# board.net
KiCad netlist of a schematic drawn in EAGLE
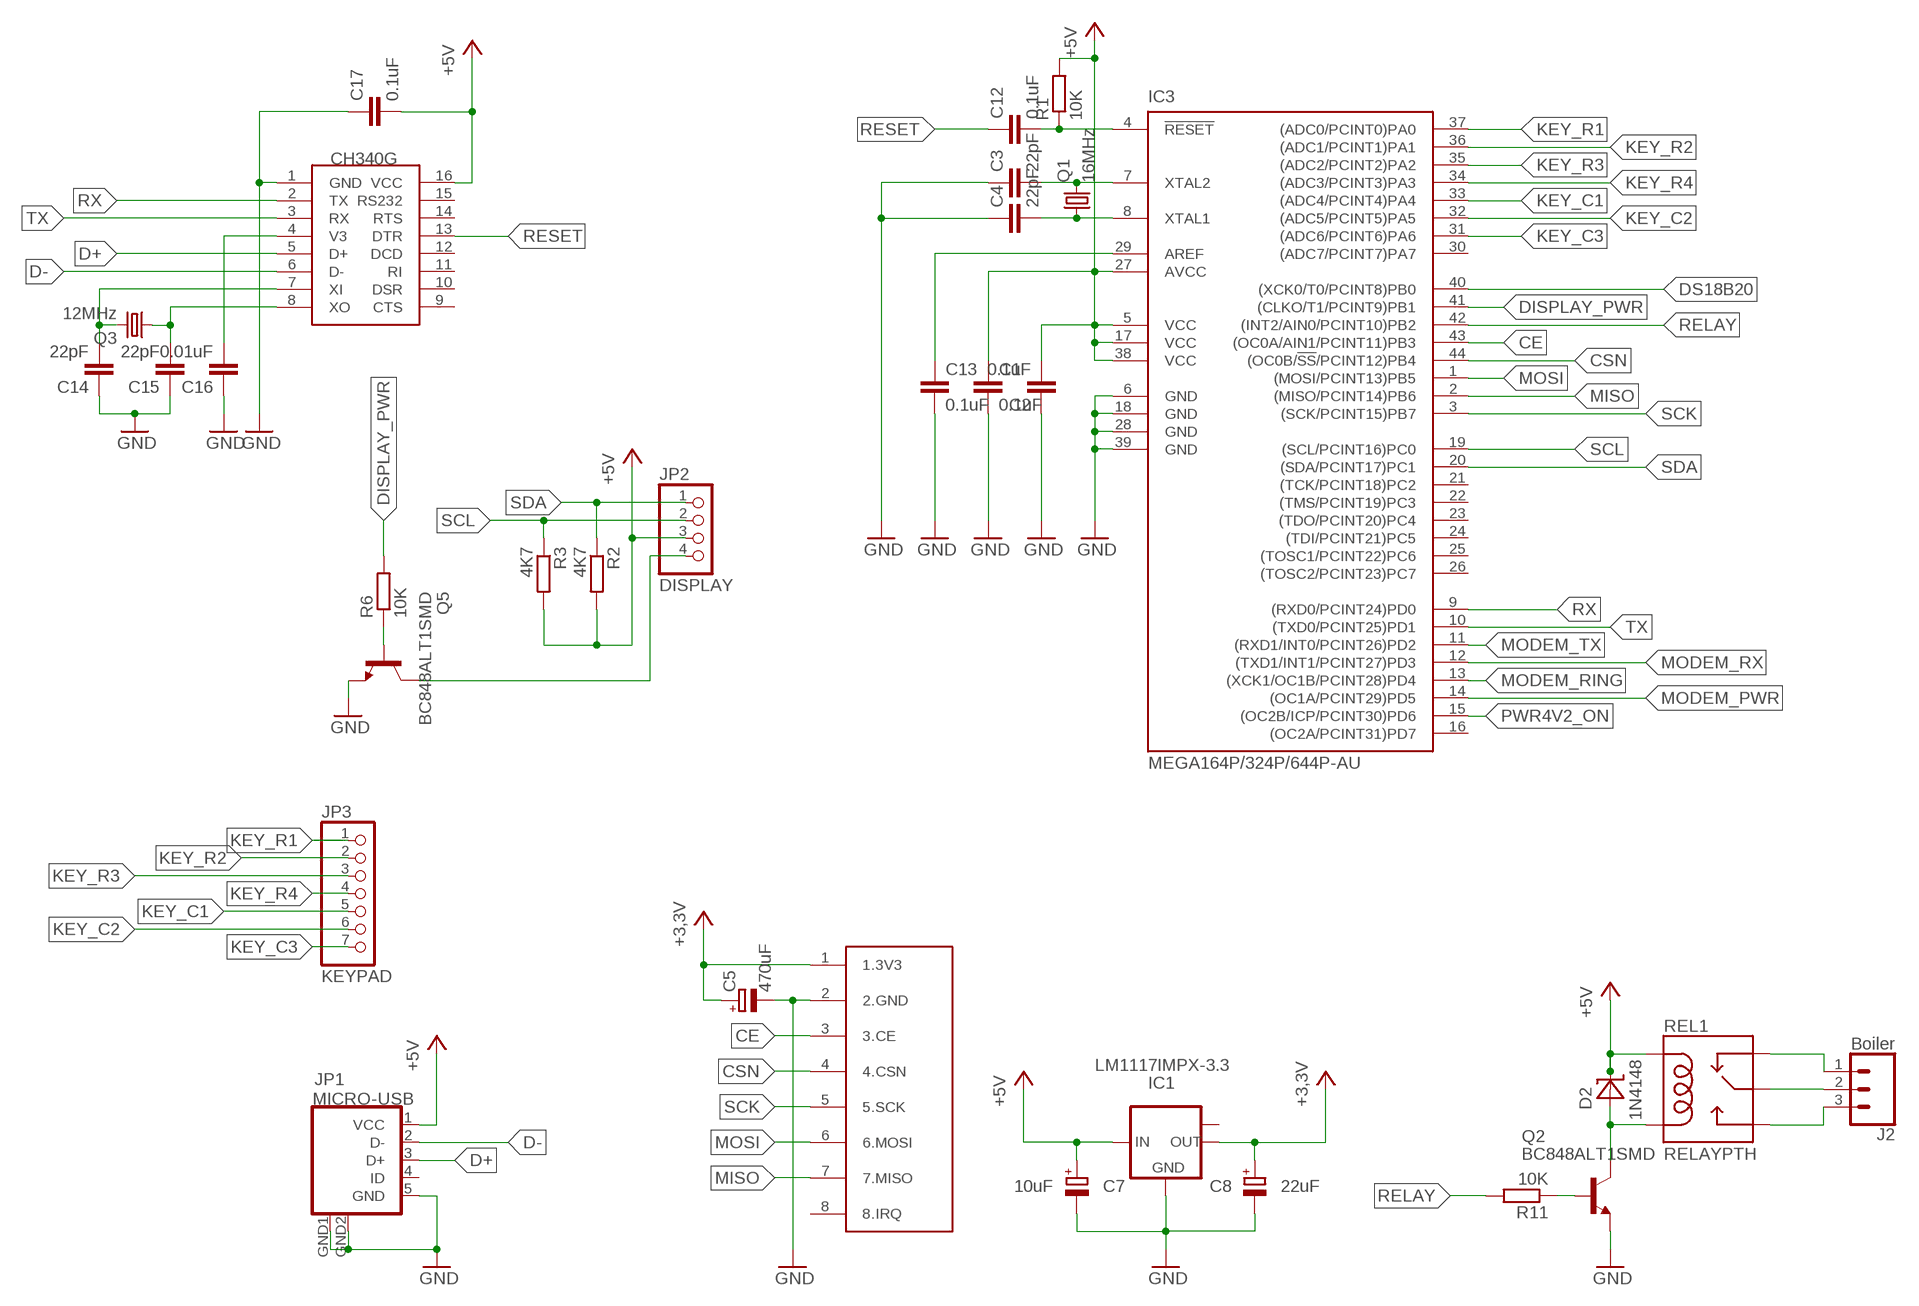
[diagram p0: schematic, sheet 1, part 1 of 2]
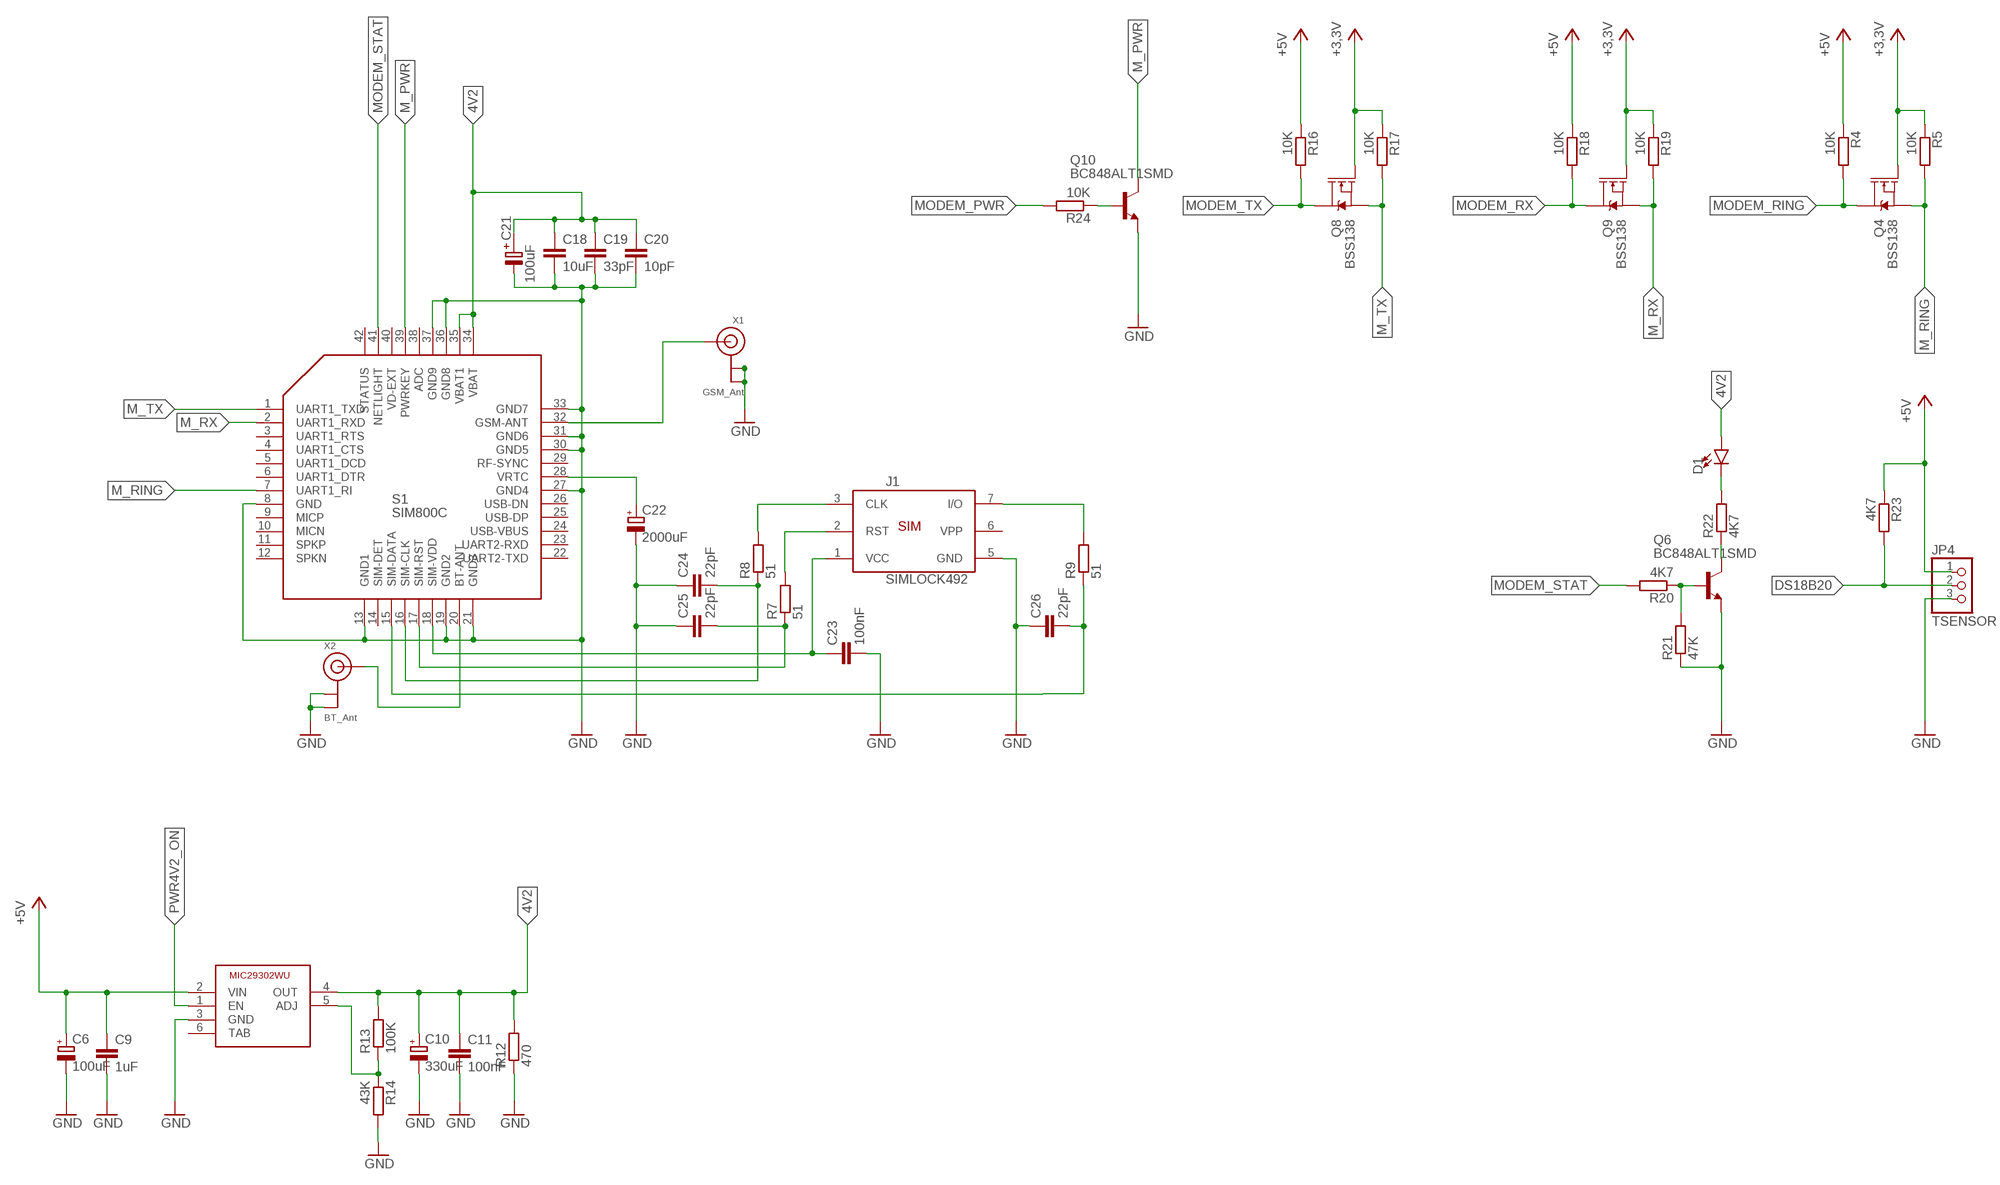
[diagram p1: schematic, sheet 1, part 2 of 2]

(export (version "E")
  (design (tool "Eeschema 10.0.6"))
  (components
    (comp (ref "C1")
      (value "0.1uF")
      (footprint "eagle-import:C1206")
      (libsource (lib "eagle-import") (part "C-EUC1206"))
    )
    (comp (ref "C2")
      (value "0.1uF")
      (footprint "eagle-import:C1206")
      (libsource (lib "eagle-import") (part "C-EUC1206"))
    )
    (comp (ref "C3")
      (value "22pF")
      (footprint "eagle-import:C1206")
      (libsource (lib "eagle-import") (part "C-EUC1206"))
    )
    (comp (ref "C4")
      (value "22pF")
      (footprint "eagle-import:C1206")
      (libsource (lib "eagle-import") (part "C-EUC1206"))
    )
    (comp (ref "C5")
      (value "470uF")
      (footprint "eagle-import:E3,5-8")
      (libsource (lib "eagle-import") (part "CPOL-EUE3.5-8"))
    )
    (comp (ref "C6")
      (value "100uF")
      (footprint "eagle-import:E1,8-4")
      (libsource (lib "eagle-import") (part "CPOL-EUE1.8-4"))
    )
    (comp (ref "C7")
      (value "10uF")
      (footprint "eagle-import:E1,8-4")
      (libsource (lib "eagle-import") (part "CPOL-EUE1.8-4"))
    )
    (comp (ref "C8")
      (value "22uF")
      (footprint "eagle-import:E1,8-4")
      (libsource (lib "eagle-import") (part "CPOL-EUE1.8-4"))
    )
    (comp (ref "C9")
      (value "1uF")
      (footprint "eagle-import:C1206")
      (libsource (lib "eagle-import") (part "C-EUC1206"))
    )
    (comp (ref "C10")
      (value "330uF")
      (footprint "eagle-import:E1,8-4")
      (libsource (lib "eagle-import") (part "CPOL-EUE1.8-4"))
    )
    (comp (ref "C11")
      (value "100nF")
      (footprint "eagle-import:C1206")
      (libsource (lib "eagle-import") (part "C-EUC1206"))
    )
    (comp (ref "C12")
      (value "0.1uF")
      (footprint "eagle-import:C1206")
      (libsource (lib "eagle-import") (part "C-EUC1206"))
    )
    (comp (ref "C13")
      (value "0.1uF")
      (footprint "eagle-import:C1206")
      (libsource (lib "eagle-import") (part "C-EUC1206"))
    )
    (comp (ref "C14")
      (value "22pF")
      (footprint "eagle-import:C1206")
      (libsource (lib "eagle-import") (part "C-EUC1206"))
    )
    (comp (ref "C15")
      (value "22pF")
      (footprint "eagle-import:C1206")
      (libsource (lib "eagle-import") (part "C-EUC1206"))
    )
    (comp (ref "C16")
      (value "0.01uF")
      (footprint "eagle-import:C1206")
      (libsource (lib "eagle-import") (part "C-EUC1206"))
    )
    (comp (ref "C17")
      (value "0.1uF")
      (footprint "eagle-import:C1206")
      (libsource (lib "eagle-import") (part "C-EUC1206"))
    )
    (comp (ref "C18")
      (value "10uF")
      (footprint "eagle-import:C1206")
      (libsource (lib "eagle-import") (part "C-EUC1206"))
    )
    (comp (ref "C19")
      (value "33pF")
      (footprint "eagle-import:C1206")
      (libsource (lib "eagle-import") (part "C-EUC1206"))
    )
    (comp (ref "C20")
      (value "10pF")
      (footprint "eagle-import:C1206")
      (libsource (lib "eagle-import") (part "C-EUC1206"))
    )
    (comp (ref "C21")
      (value "100uF")
      (footprint "eagle-import:TE-D-7343")
      (libsource (lib "eagle-import") (part "C-PR-SMD-TE-D"))
    )
    (comp (ref "C22")
      (value "2000uF")
      (footprint "eagle-import:E3,5-8")
      (libsource (lib "eagle-import") (part "CPOL-EUE3.5-8"))
    )
    (comp (ref "C23")
      (value "100nF")
      (footprint "eagle-import:C1206")
      (libsource (lib "eagle-import") (part "C-EUC1206"))
    )
    (comp (ref "C24")
      (value "22pF")
      (footprint "eagle-import:C1206")
      (libsource (lib "eagle-import") (part "C-EUC1206"))
    )
    (comp (ref "C25")
      (value "22pF")
      (footprint "eagle-import:C1206")
      (libsource (lib "eagle-import") (part "C-EUC1206"))
    )
    (comp (ref "C26")
      (value "22pF")
      (footprint "eagle-import:C1206")
      (libsource (lib "eagle-import") (part "C-EUC1206"))
    )
    (comp (ref "D1")
      (value "LED1206")
      (footprint "eagle-import:LED-1206")
      (libsource (lib "eagle-import") (part "LED1206"))
    )
    (comp (ref "D2")
      (value "1N4148")
      (footprint "eagle-import:SOD323-W")
      (libsource (lib "eagle-import") (part "1206ZENERSOD323"))
    )
    (comp (ref "IC1")
      (value "LM1117IMPX-3.3")
      (footprint "eagle-import:SOT223")
      (libsource (lib "eagle-import") (part "LM1117IMPX-3.3"))
    )
    (comp (ref "IC2")
      (value "MIC29302WU")
      (footprint "eagle-import:TO263-5")
      (fields (field (name "MF") "Microchip"))
      (libsource (lib "eagle-import") (part "MIC29302WU"))
    )
    (comp (ref "IC3")
      (value "MEGA164P/324P/644P-AU")
      (footprint "eagle-import:TQFP44")
      (libsource (lib "eagle-import") (part "MEGA164P/324P/644P-AU"))
    )
    (comp (ref "J1")
      (value "SIMLOCK492")
      (footprint "eagle-import:5002")
      (libsource (lib "eagle-import") (part "SIMLOCK492"))
    )
    (comp (ref "J2")
      (value "Boiler")
      (footprint "eagle-import:SCREWTERMINAL-5MM-3")
      (libsource (lib "eagle-import") (part "CONN_03-SCREW-5MM"))
    )
    (comp (ref "JP1")
      (value "MICRO-USB")
      (footprint "eagle-import:MICRO-USB")
      (libsource (lib "eagle-import") (part "MICRO-USB"))
    )
    (comp (ref "JP2")
      (value "DISPLAY")
      (footprint "eagle-import:1X04")
      (libsource (lib "eagle-import") (part "PINHD-1X4"))
    )
    (comp (ref "JP3")
      (value "KEYPAD")
      (footprint "eagle-import:1X07")
      (libsource (lib "eagle-import") (part "PINHD-1X7"))
    )
    (comp (ref "JP4")
      (value "TSENSOR")
      (footprint "eagle-import:1X03")
      (libsource (lib "eagle-import") (part "PINHD-1X3"))
    )
    (comp (ref "Q1")
      (value "16MHz")
      (footprint "eagle-import:HC49_S")
      (libsource (lib "eagle-import") (part "CRYTALHC49S"))
    )
    (comp (ref "Q2")
      (value "BC848ALT1SMD")
      (footprint "eagle-import:SOT23")
      (libsource (lib "eagle-import") (part "BC848SMDALT1"))
    )
    (comp (ref "Q3")
      (value "12MHz")
      (footprint "eagle-import:HC49_S")
      (libsource (lib "eagle-import") (part "CRYTALHC49S"))
    )
    (comp (ref "Q4")
      (value "BSS138")
      (footprint "eagle-import:SOT23-3")
      (libsource (lib "eagle-import") (part "MOSFET-NCH-BSS138"))
    )
    (comp (ref "Q5")
      (value "BC848ALT1SMD")
      (footprint "eagle-import:SOT23")
      (libsource (lib "eagle-import") (part "BC848SMDALT1"))
    )
    (comp (ref "Q6")
      (value "BC848ALT1SMD")
      (footprint "eagle-import:SOT23")
      (libsource (lib "eagle-import") (part "BC848SMDALT1"))
    )
    (comp (ref "Q8")
      (value "BSS138")
      (footprint "eagle-import:SOT23-3")
      (libsource (lib "eagle-import") (part "MOSFET-NCH-BSS138"))
    )
    (comp (ref "Q9")
      (value "BSS138")
      (footprint "eagle-import:SOT23-3")
      (libsource (lib "eagle-import") (part "MOSFET-NCH-BSS138"))
    )
    (comp (ref "Q10")
      (value "BC848ALT1SMD")
      (footprint "eagle-import:SOT23")
      (libsource (lib "eagle-import") (part "BC848SMDALT1"))
    )
    (comp (ref "R1")
      (value "10K")
      (footprint "eagle-import:R1206")
      (libsource (lib "eagle-import") (part "R-EU_R1206"))
    )
    (comp (ref "R2")
      (value "4K7")
      (footprint "eagle-import:R1206")
      (libsource (lib "eagle-import") (part "R-EU_R1206"))
    )
    (comp (ref "R3")
      (value "4K7")
      (footprint "eagle-import:R1206")
      (libsource (lib "eagle-import") (part "R-EU_R1206"))
    )
    (comp (ref "R4")
      (value "10K")
      (footprint "eagle-import:R1206")
      (libsource (lib "eagle-import") (part "R-EU_R1206"))
    )
    (comp (ref "R5")
      (value "10K")
      (footprint "eagle-import:R1206")
      (libsource (lib "eagle-import") (part "R-EU_R1206"))
    )
    (comp (ref "R6")
      (value "10K")
      (footprint "eagle-import:R1206")
      (libsource (lib "eagle-import") (part "R-EU_R1206"))
    )
    (comp (ref "R7")
      (value "51")
      (footprint "eagle-import:R1206")
      (libsource (lib "eagle-import") (part "R-EU_R1206"))
    )
    (comp (ref "R8")
      (value "51")
      (footprint "eagle-import:R1206")
      (libsource (lib "eagle-import") (part "R-EU_R1206"))
    )
    (comp (ref "R9")
      (value "51")
      (footprint "eagle-import:R1206")
      (libsource (lib "eagle-import") (part "R-EU_R1206"))
    )
    (comp (ref "R11")
      (value "10K")
      (footprint "eagle-import:R1206")
      (libsource (lib "eagle-import") (part "R-EU_R1206"))
    )
    (comp (ref "R12")
      (value "470")
      (footprint "eagle-import:R1206")
      (libsource (lib "eagle-import") (part "R-EU_R1206"))
    )
    (comp (ref "R13")
      (value "100K")
      (footprint "eagle-import:R1206")
      (libsource (lib "eagle-import") (part "R-EU_R1206"))
    )
    (comp (ref "R14")
      (value "43K")
      (footprint "eagle-import:R1206")
      (libsource (lib "eagle-import") (part "R-EU_R1206"))
    )
    (comp (ref "R16")
      (value "10K")
      (footprint "eagle-import:R1206")
      (libsource (lib "eagle-import") (part "R-EU_R1206"))
    )
    (comp (ref "R17")
      (value "10K")
      (footprint "eagle-import:R1206")
      (libsource (lib "eagle-import") (part "R-EU_R1206"))
    )
    (comp (ref "R18")
      (value "10K")
      (footprint "eagle-import:R1206")
      (libsource (lib "eagle-import") (part "R-EU_R1206"))
    )
    (comp (ref "R19")
      (value "10K")
      (footprint "eagle-import:R1206")
      (libsource (lib "eagle-import") (part "R-EU_R1206"))
    )
    (comp (ref "R20")
      (value "4K7")
      (footprint "eagle-import:R1206")
      (libsource (lib "eagle-import") (part "R-EU_R1206"))
    )
    (comp (ref "R21")
      (value "47K")
      (footprint "eagle-import:R1206")
      (libsource (lib "eagle-import") (part "R-EU_R1206"))
    )
    (comp (ref "R22")
      (value "4K7")
      (footprint "eagle-import:R1206")
      (libsource (lib "eagle-import") (part "R-EU_R1206"))
    )
    (comp (ref "R23")
      (value "4K7")
      (footprint "eagle-import:R1206")
      (libsource (lib "eagle-import") (part "R-EU_R1206"))
    )
    (comp (ref "R24")
      (value "10K")
      (footprint "eagle-import:R1206")
      (libsource (lib "eagle-import") (part "R-EU_R1206"))
    )
    (comp (ref "REL1")
      (value "RELAYPTH")
      (footprint "eagle-import:SRD-05VDC-SL-C")
      (libsource (lib "eagle-import") (part "RELAYPTH"))
    )
    (comp (ref "S1")
      (value "SIM800C")
      (footprint "eagle-import:SIM800C")
      (libsource (lib "eagle-import") (part "SIM800C"))
    )
    (comp (ref "U$1")
      (value "CH340G")
      (footprint "eagle-import:SOIC16")
      (libsource (lib "eagle-import") (part "CH340G"))
    )
    (comp (ref "U$3")
      (value "NRF24L01+")
      (footprint "eagle-import:NRF24L01+")
      (libsource (lib "eagle-import") (part "NRF24L01+"))
    )
    (comp (ref "X1")
      (value "GSM_Ant")
      (footprint "eagle-import:U.FL")
      (libsource (lib "eagle-import") (part "ANTENNA_U.FL"))
    )
    (comp (ref "X2")
      (value "BT_Ant")
      (footprint "eagle-import:U.FL")
      (libsource (lib "eagle-import") (part "ANTENNA_U.FL"))
    )
  )
  (nets
    (net (code "1") (name "+3,3V") (class "Default")
      (node (ref "C5") (pin "+") (pinfunction "+_+") (pintype "passive"))
      (node (ref "C8") (pin "+") (pinfunction "+_+") (pintype "passive"))
      (node (ref "IC1") (pin "2") (pinfunction "OUT_2") (pintype "passive"))
      (node (ref "Q4") (pin "1") (pinfunction "G_1") (pintype "bidirectional"))
      (node (ref "Q8") (pin "1") (pinfunction "G_1") (pintype "bidirectional"))
      (node (ref "Q9") (pin "1") (pinfunction "G_1") (pintype "bidirectional"))
      (node (ref "R17") (pin "1") (pinfunction "1_1") (pintype "passive"))
      (node (ref "R19") (pin "1") (pinfunction "1_1") (pintype "passive"))
      (node (ref "R5") (pin "1") (pinfunction "1_1") (pintype "passive"))
      (node (ref "U$3") (pin "1") (pinfunction "1.3V3_1") (pintype "bidirectional"))
    )
    (net (code "2") (name "+5V") (class "Default")
      (node (ref "C1") (pin "1") (pinfunction "1_1") (pintype "passive"))
      (node (ref "C17") (pin "2") (pinfunction "2_2") (pintype "passive"))
      (node (ref "C2") (pin "2") (pinfunction "2_2") (pintype "passive"))
      (node (ref "C6") (pin "+") (pinfunction "+_+") (pintype "passive"))
      (node (ref "C7") (pin "+") (pinfunction "+_+") (pintype "passive"))
      (node (ref "C9") (pin "1") (pinfunction "1_1") (pintype "passive"))
      (node (ref "D2") (pin "C") (pinfunction "C_C") (pintype "passive"))
      (node (ref "IC1") (pin "3") (pinfunction "IN_3") (pintype "input"))
      (node (ref "IC2") (pin "2") (pinfunction "VIN_2") (pintype "bidirectional"))
      (node (ref "IC3") (pin "17") (pinfunction "VCC_17") (pintype "power_in"))
      (node (ref "IC3") (pin "27") (pinfunction "AVCC_27") (pintype "power_in"))
      (node (ref "IC3") (pin "38") (pinfunction "VCC_38") (pintype "power_in"))
      (node (ref "IC3") (pin "5") (pinfunction "VCC_5") (pintype "power_in"))
      (node (ref "JP1") (pin "1") (pinfunction "VCC_1") (pintype "power_in"))
      (node (ref "JP2") (pin "3") (pinfunction "3_3") (pintype "passive"))
      (node (ref "JP4") (pin "1") (pinfunction "1_1") (pintype "passive"))
      (node (ref "R1") (pin "2") (pinfunction "2_2") (pintype "passive"))
      (node (ref "R16") (pin "1") (pinfunction "1_1") (pintype "passive"))
      (node (ref "R18") (pin "1") (pinfunction "1_1") (pintype "passive"))
      (node (ref "R2") (pin "2") (pinfunction "2_2") (pintype "passive"))
      (node (ref "R23") (pin "1") (pinfunction "1_1") (pintype "passive"))
      (node (ref "R3") (pin "2") (pinfunction "2_2") (pintype "passive"))
      (node (ref "R4") (pin "1") (pinfunction "1_1") (pintype "passive"))
      (node (ref "REL1") (pin "COIL1") (pinfunction "COIL1_COIL1") (pintype "bidirectional"))
      (node (ref "U$1") (pin "16") (pinfunction "VCC_16") (pintype "bidirectional"))
    )
    (net (code "3") (name "4V2") (class "Default")
      (node (ref "C10") (pin "+") (pinfunction "+_+") (pintype "passive"))
      (node (ref "C11") (pin "1") (pinfunction "1_1") (pintype "passive"))
      (node (ref "C18") (pin "1") (pinfunction "1_1") (pintype "passive"))
      (node (ref "C19") (pin "1") (pinfunction "1_1") (pintype "passive"))
      (node (ref "C20") (pin "1") (pinfunction "1_1") (pintype "passive"))
      (node (ref "C21") (pin "+") (pinfunction "+_+") (pintype "passive"))
      (node (ref "D1") (pin "A") (pinfunction "A_A") (pintype "passive"))
      (node (ref "IC2") (pin "4") (pinfunction "OUT_4") (pintype "bidirectional"))
      (node (ref "R12") (pin "2") (pinfunction "2_2") (pintype "passive"))
      (node (ref "R13") (pin "2") (pinfunction "2_2") (pintype "passive"))
      (node (ref "S1") (pin "34") (pinfunction "VBAT_34") (pintype "power_in"))
      (node (ref "S1") (pin "35") (pinfunction "VBAT1_35") (pintype "power_in"))
    )
    (net (code "4") (name "CE") (class "Default")
      (node (ref "IC3") (pin "43") (pinfunction "(OC0A/AIN1/PCINT11)PB3_43") (pintype "bidirectional"))
      (node (ref "U$3") (pin "3") (pinfunction "3.CE_3") (pintype "bidirectional"))
    )
    (net (code "5") (name "CSN") (class "Default")
      (node (ref "IC3") (pin "44") (pinfunction "(OC0B/~{SS}/PCINT12)PB4_44") (pintype "bidirectional"))
      (node (ref "U$3") (pin "4") (pinfunction "4.CSN_4") (pintype "bidirectional"))
    )
    (net (code "6") (name "D+") (class "Default")
      (node (ref "JP1") (pin "3") (pinfunction "D+_3") (pintype "bidirectional"))
      (node (ref "U$1") (pin "5") (pinfunction "D+_5") (pintype "bidirectional"))
    )
    (net (code "7") (name "D-") (class "Default")
      (node (ref "JP1") (pin "2") (pinfunction "D-_2") (pintype "bidirectional"))
      (node (ref "U$1") (pin "6") (pinfunction "D-_6") (pintype "bidirectional"))
    )
    (net (code "8") (name "DISPLAY_PWR") (class "Default")
      (node (ref "IC3") (pin "41") (pinfunction "(CLKO/T1/PCINT9)PB1_41") (pintype "bidirectional"))
      (node (ref "R6") (pin "2") (pinfunction "2_2") (pintype "passive"))
    )
    (net (code "9") (name "DS18B20") (class "Default")
      (node (ref "IC3") (pin "40") (pinfunction "(XCK0/T0/PCINT8)PB0_40") (pintype "bidirectional"))
      (node (ref "JP4") (pin "2") (pinfunction "2_2") (pintype "passive"))
      (node (ref "R23") (pin "2") (pinfunction "2_2") (pintype "passive"))
    )
    (net (code "10") (name "GND") (class "Default")
      (node (ref "C1") (pin "2") (pinfunction "2_2") (pintype "passive"))
      (node (ref "C10") (pin "-") (pinfunction "-_-") (pintype "passive"))
      (node (ref "C11") (pin "2") (pinfunction "2_2") (pintype "passive"))
      (node (ref "C13") (pin "2") (pinfunction "2_2") (pintype "passive"))
      (node (ref "C14") (pin "1") (pinfunction "1_1") (pintype "passive"))
      (node (ref "C15") (pin "1") (pinfunction "1_1") (pintype "passive"))
      (node (ref "C16") (pin "1") (pinfunction "1_1") (pintype "passive"))
      (node (ref "C17") (pin "1") (pinfunction "1_1") (pintype "passive"))
      (node (ref "C18") (pin "2") (pinfunction "2_2") (pintype "passive"))
      (node (ref "C19") (pin "2") (pinfunction "2_2") (pintype "passive"))
      (node (ref "C2") (pin "1") (pinfunction "1_1") (pintype "passive"))
      (node (ref "C20") (pin "2") (pinfunction "2_2") (pintype "passive"))
      (node (ref "C21") (pin "-") (pinfunction "-_-") (pintype "passive"))
      (node (ref "C22") (pin "-") (pinfunction "-_-") (pintype "passive"))
      (node (ref "C23") (pin "2") (pinfunction "2_2") (pintype "passive"))
      (node (ref "C24") (pin "1") (pinfunction "1_1") (pintype "passive"))
      (node (ref "C25") (pin "1") (pinfunction "1_1") (pintype "passive"))
      (node (ref "C26") (pin "1") (pinfunction "1_1") (pintype "passive"))
      (node (ref "C3") (pin "1") (pinfunction "1_1") (pintype "passive"))
      (node (ref "C4") (pin "1") (pinfunction "1_1") (pintype "passive"))
      (node (ref "C5") (pin "-") (pinfunction "-_-") (pintype "passive"))
      (node (ref "C6") (pin "-") (pinfunction "-_-") (pintype "passive"))
      (node (ref "C7") (pin "-") (pinfunction "-_-") (pintype "passive"))
      (node (ref "C8") (pin "-") (pinfunction "-_-") (pintype "passive"))
      (node (ref "C9") (pin "2") (pinfunction "2_2") (pintype "passive"))
      (node (ref "IC1") (pin "1") (pinfunction "GND_1") (pintype "input"))
      (node (ref "IC2") (pin "3") (pinfunction "GND_3") (pintype "bidirectional"))
      (node (ref "IC3") (pin "18") (pinfunction "GND_18") (pintype "power_in"))
      (node (ref "IC3") (pin "28") (pinfunction "GND_28") (pintype "power_in"))
      (node (ref "IC3") (pin "39") (pinfunction "GND_39") (pintype "power_in"))
      (node (ref "IC3") (pin "6") (pinfunction "GND_6") (pintype "power_in"))
      (node (ref "J1") (pin "5") (pinfunction "GND_5") (pintype "bidirectional"))
      (node (ref "JP1") (pin "5") (pinfunction "GND_5") (pintype "power_in"))
      (node (ref "JP1") (pin "GND1") (pinfunction "GND_GND1") (pintype "power_in"))
      (node (ref "JP1") (pin "GND2") (pinfunction "GND_GND2") (pintype "power_in"))
      (node (ref "JP4") (pin "3") (pinfunction "3_3") (pintype "passive"))
      (node (ref "Q10") (pin "2") (pinfunction "E_2") (pintype "passive"))
      (node (ref "Q2") (pin "2") (pinfunction "E_2") (pintype "passive"))
      (node (ref "Q5") (pin "2") (pinfunction "E_2") (pintype "passive"))
      (node (ref "Q6") (pin "2") (pinfunction "E_2") (pintype "passive"))
      (node (ref "R12") (pin "1") (pinfunction "1_1") (pintype "passive"))
      (node (ref "R14") (pin "2") (pinfunction "2_2") (pintype "passive"))
      (node (ref "R21") (pin "1") (pinfunction "1_1") (pintype "passive"))
      (node (ref "S1") (pin "13") (pinfunction "GND1_13") (pintype "power_in"))
      (node (ref "S1") (pin "19") (pinfunction "GND2_19") (pintype "power_in"))
      (node (ref "S1") (pin "21") (pinfunction "GND3_21") (pintype "power_in"))
      (node (ref "S1") (pin "27") (pinfunction "GND4_27") (pintype "power_in"))
      (node (ref "S1") (pin "30") (pinfunction "GND5_30") (pintype "power_in"))
      (node (ref "S1") (pin "31") (pinfunction "GND6_31") (pintype "power_in"))
      (node (ref "S1") (pin "33") (pinfunction "GND7_33") (pintype "power_in"))
      (node (ref "S1") (pin "36") (pinfunction "GND8_36") (pintype "power_in"))
      (node (ref "S1") (pin "37") (pinfunction "GND9_37") (pintype "power_in"))
      (node (ref "S1") (pin "8") (pinfunction "GND_8") (pintype "power_in"))
      (node (ref "U$1") (pin "1") (pinfunction "GND_1") (pintype "bidirectional"))
      (node (ref "U$3") (pin "2") (pinfunction "2.GND_2") (pintype "bidirectional"))
      (node (ref "X1") (pin "1") (pinfunction "GND_1") (pintype "passive"))
      (node (ref "X1") (pin "2") (pinfunction "GND_2") (pintype "passive"))
      (node (ref "X2") (pin "1") (pinfunction "GND_1") (pintype "passive"))
      (node (ref "X2") (pin "2") (pinfunction "GND_2") (pintype "passive"))
    )
    (net (code "11") (name "KEY_C1") (class "Default")
      (node (ref "IC3") (pin "33") (pinfunction "(ADC4/PCINT4)PA4_33") (pintype "bidirectional"))
      (node (ref "JP3") (pin "5") (pinfunction "5_5") (pintype "passive"))
    )
    (net (code "12") (name "KEY_C2") (class "Default")
      (node (ref "IC3") (pin "32") (pinfunction "(ADC5/PCINT5)PA5_32") (pintype "bidirectional"))
      (node (ref "JP3") (pin "6") (pinfunction "6_6") (pintype "passive"))
    )
    (net (code "13") (name "KEY_C3") (class "Default")
      (node (ref "IC3") (pin "31") (pinfunction "(ADC6/PCINT6)PA6_31") (pintype "bidirectional"))
      (node (ref "JP3") (pin "7") (pinfunction "7_7") (pintype "passive"))
    )
    (net (code "14") (name "KEY_R1") (class "Default")
      (node (ref "IC3") (pin "37") (pinfunction "(ADC0/PCINT0)PA0_37") (pintype "bidirectional"))
      (node (ref "JP3") (pin "1") (pinfunction "1_1") (pintype "passive"))
    )
    (net (code "15") (name "KEY_R2") (class "Default")
      (node (ref "IC3") (pin "36") (pinfunction "(ADC1/PCINT1)PA1_36") (pintype "bidirectional"))
      (node (ref "JP3") (pin "2") (pinfunction "2_2") (pintype "passive"))
    )
    (net (code "16") (name "KEY_R3") (class "Default")
      (node (ref "IC3") (pin "35") (pinfunction "(ADC2/PCINT2)PA2_35") (pintype "bidirectional"))
      (node (ref "JP3") (pin "3") (pinfunction "3_3") (pintype "passive"))
    )
    (net (code "17") (name "KEY_R4") (class "Default")
      (node (ref "IC3") (pin "34") (pinfunction "(ADC3/PCINT3)PA3_34") (pintype "bidirectional"))
      (node (ref "JP3") (pin "4") (pinfunction "4_4") (pintype "passive"))
    )
    (net (code "18") (name "MISO") (class "Default")
      (node (ref "IC3") (pin "2") (pinfunction "(MISO/PCINT14)PB6_2") (pintype "bidirectional"))
      (node (ref "U$3") (pin "7") (pinfunction "7.MISO_7") (pintype "bidirectional"))
    )
    (net (code "19") (name "MODEM_PWR") (class "Default")
      (node (ref "IC3") (pin "14") (pinfunction "(OC1A/PCINT29)PD5_14") (pintype "bidirectional"))
      (node (ref "R24") (pin "2") (pinfunction "2_2") (pintype "passive"))
    )
    (net (code "20") (name "MODEM_RING") (class "Default")
      (node (ref "IC3") (pin "13") (pinfunction "(XCK1/OC1B/PCINT28)PD4_13") (pintype "bidirectional"))
      (node (ref "Q4") (pin "3") (pinfunction "D_3") (pintype "bidirectional"))
      (node (ref "R4") (pin "2") (pinfunction "2_2") (pintype "passive"))
    )
    (net (code "21") (name "MODEM_RX") (class "Default")
      (node (ref "IC3") (pin "12") (pinfunction "(TXD1/INT1/PCINT27)PD3_12") (pintype "bidirectional"))
      (node (ref "Q9") (pin "3") (pinfunction "D_3") (pintype "bidirectional"))
      (node (ref "R18") (pin "2") (pinfunction "2_2") (pintype "passive"))
    )
    (net (code "22") (name "MODEM_STAT") (class "Default")
      (node (ref "R20") (pin "2") (pinfunction "2_2") (pintype "passive"))
      (node (ref "S1") (pin "41") (pinfunction "NETLIGHT_41") (pintype "bidirectional"))
    )
    (net (code "23") (name "MODEM_TX") (class "Default")
      (node (ref "IC3") (pin "11") (pinfunction "(RXD1/INT0/PCINT26)PD2_11") (pintype "bidirectional"))
      (node (ref "Q8") (pin "3") (pinfunction "D_3") (pintype "bidirectional"))
      (node (ref "R16") (pin "2") (pinfunction "2_2") (pintype "passive"))
    )
    (net (code "24") (name "MOSI") (class "Default")
      (node (ref "IC3") (pin "1") (pinfunction "(MOSI/PCINT13)PB5_1") (pintype "bidirectional"))
      (node (ref "U$3") (pin "6") (pinfunction "6.MOSI_6") (pintype "bidirectional"))
    )
    (net (code "25") (name "M_PWR") (class "Default")
      (node (ref "Q10") (pin "3") (pinfunction "C_3") (pintype "passive"))
      (node (ref "S1") (pin "39") (pinfunction "PWRKEY_39") (pintype "bidirectional"))
    )
    (net (code "26") (name "M_RING") (class "Default")
      (node (ref "Q4") (pin "2") (pinfunction "S_2") (pintype "bidirectional"))
      (node (ref "R5") (pin "2") (pinfunction "2_2") (pintype "passive"))
      (node (ref "S1") (pin "7") (pinfunction "UART1_RI_7") (pintype "bidirectional"))
    )
    (net (code "27") (name "M_RX") (class "Default")
      (node (ref "Q9") (pin "2") (pinfunction "S_2") (pintype "bidirectional"))
      (node (ref "R19") (pin "2") (pinfunction "2_2") (pintype "passive"))
      (node (ref "S1") (pin "2") (pinfunction "UART1_RXD_2") (pintype "bidirectional"))
    )
    (net (code "28") (name "M_TX") (class "Default")
      (node (ref "Q8") (pin "2") (pinfunction "S_2") (pintype "bidirectional"))
      (node (ref "R17") (pin "2") (pinfunction "2_2") (pintype "passive"))
      (node (ref "S1") (pin "1") (pinfunction "UART1_TXD_1") (pintype "bidirectional"))
    )
    (net (code "29") (name "Net-(D1-PadC)") (class "Default")
      (node (ref "D1") (pin "C") (pinfunction "C_C") (pintype "passive"))
      (node (ref "R22") (pin "2") (pinfunction "2_2") (pintype "passive"))
    )
    (net (code "30") (name "Net-(IC2-ADJ)") (class "Default")
      (node (ref "IC2") (pin "5") (pinfunction "ADJ_5") (pintype "bidirectional"))
      (node (ref "R13") (pin "1") (pinfunction "1_1") (pintype "passive"))
      (node (ref "R14") (pin "1") (pinfunction "1_1") (pintype "passive"))
    )
    (net (code "31") (name "Net-(IC3-AREF)") (class "Default")
      (node (ref "C13") (pin "1") (pinfunction "1_1") (pintype "passive"))
      (node (ref "IC3") (pin "29") (pinfunction "AREF_29") (pintype "power_in"))
    )
    (net (code "32") (name "Net-(IC3-XTAL1)") (class "Default")
      (node (ref "C4") (pin "2") (pinfunction "2_2") (pintype "passive"))
      (node (ref "IC3") (pin "8") (pinfunction "XTAL1_8") (pintype "input"))
      (node (ref "Q1") (pin "1") (pinfunction "1_1") (pintype "passive"))
    )
    (net (code "33") (name "Net-(IC3-XTAL2)") (class "Default")
      (node (ref "C3") (pin "2") (pinfunction "2_2") (pintype "passive"))
      (node (ref "IC3") (pin "7") (pinfunction "XTAL2_7") (pintype "output"))
      (node (ref "Q1") (pin "2") (pinfunction "2_2") (pintype "passive"))
    )
    (net (code "34") (name "Net-(IC3-~{RESET})") (class "Default")
      (node (ref "C12") (pin "2") (pinfunction "2_2") (pintype "passive"))
      (node (ref "IC3") (pin "4") (pinfunction "~{RESET}_4") (pintype "input"))
      (node (ref "R1") (pin "1") (pinfunction "1_1") (pintype "passive"))
    )
    (net (code "35") (name "Net-(J1-CLK)") (class "Default")
      (node (ref "J1") (pin "3") (pinfunction "CLK_3") (pintype "bidirectional"))
      (node (ref "R8") (pin "2") (pinfunction "2_2") (pintype "passive"))
    )
    (net (code "36") (name "Net-(J1-I{slash}O)") (class "Default")
      (node (ref "J1") (pin "7") (pinfunction "I/O_7") (pintype "bidirectional"))
      (node (ref "R9") (pin "2") (pinfunction "2_2") (pintype "passive"))
    )
    (net (code "37") (name "Net-(J1-RST)") (class "Default")
      (node (ref "J1") (pin "2") (pinfunction "RST_2") (pintype "bidirectional"))
      (node (ref "R7") (pin "2") (pinfunction "2_2") (pintype "passive"))
    )
    (net (code "38") (name "Net-(J1-VCC)") (class "Default")
      (node (ref "C23") (pin "1") (pinfunction "1_1") (pintype "passive"))
      (node (ref "J1") (pin "1") (pinfunction "VCC_1") (pintype "bidirectional"))
      (node (ref "S1") (pin "18") (pinfunction "SIM-VDD_18") (pintype "bidirectional"))
    )
    (net (code "39") (name "Net-(J2-Pad2)") (class "Default")
      (node (ref "J2") (pin "2") (pinfunction "2_2") (pintype "passive"))
      (node (ref "REL1") (pin "SWCOMMON") (pinfunction "SWCOMMON_SWCOMMON") (pintype "bidirectional"))
    )
    (net (code "40") (name "Net-(J2-Pad3)") (class "Default")
      (node (ref "J2") (pin "3") (pinfunction "3_3") (pintype "passive"))
      (node (ref "REL1") (pin "SWOPEN") (pinfunction "SWOPEN_SWOPEN") (pintype "bidirectional"))
    )
    (net (code "41") (name "Net-(Q2-B)") (class "Default")
      (node (ref "Q2") (pin "1") (pinfunction "B_1") (pintype "passive"))
      (node (ref "R11") (pin "1") (pinfunction "1_1") (pintype "passive"))
    )
    (net (code "42") (name "Net-(Q2-C)") (class "Default")
      (node (ref "D2") (pin "A") (pinfunction "A_A") (pintype "passive"))
      (node (ref "Q2") (pin "3") (pinfunction "C_3") (pintype "passive"))
      (node (ref "REL1") (pin "COIL0") (pinfunction "COIL0_COIL0") (pintype "bidirectional"))
    )
    (net (code "43") (name "Net-(Q5-B)") (class "Default")
      (node (ref "Q5") (pin "1") (pinfunction "B_1") (pintype "passive"))
      (node (ref "R6") (pin "1") (pinfunction "1_1") (pintype "passive"))
    )
    (net (code "44") (name "Net-(Q5-C)") (class "Default")
      (node (ref "JP2") (pin "4") (pinfunction "4_4") (pintype "passive"))
      (node (ref "Q5") (pin "3") (pinfunction "C_3") (pintype "passive"))
    )
    (net (code "45") (name "Net-(Q6-B)") (class "Default")
      (node (ref "Q6") (pin "1") (pinfunction "B_1") (pintype "passive"))
      (node (ref "R20") (pin "1") (pinfunction "1_1") (pintype "passive"))
      (node (ref "R21") (pin "2") (pinfunction "2_2") (pintype "passive"))
    )
    (net (code "46") (name "Net-(Q6-C)") (class "Default")
      (node (ref "Q6") (pin "3") (pinfunction "C_3") (pintype "passive"))
      (node (ref "R22") (pin "1") (pinfunction "1_1") (pintype "passive"))
    )
    (net (code "47") (name "Net-(Q10-B)") (class "Default")
      (node (ref "Q10") (pin "1") (pinfunction "B_1") (pintype "passive"))
      (node (ref "R24") (pin "1") (pinfunction "1_1") (pintype "passive"))
    )
    (net (code "48") (name "Net-(REL1-SWCLOSE)") (class "Default")
      (node (ref "J2") (pin "1") (pinfunction "1_1") (pintype "passive"))
      (node (ref "REL1") (pin "SWCLOSED") (pinfunction "SWCLOSE_SWCLOSED") (pintype "bidirectional"))
    )
    (net (code "49") (name "Net-(S1-BT-ANT)") (class "Default")
      (node (ref "S1") (pin "20") (pinfunction "BT-ANT_20") (pintype "bidirectional"))
      (node (ref "X2") (pin "3") (pinfunction "SIGNAL_3") (pintype "passive"))
    )
    (net (code "50") (name "Net-(S1-GSM-ANT)") (class "Default")
      (node (ref "S1") (pin "32") (pinfunction "GSM-ANT_32") (pintype "bidirectional"))
      (node (ref "X1") (pin "3") (pinfunction "SIGNAL_3") (pintype "passive"))
    )
    (net (code "51") (name "Net-(S1-SIM-CLK)") (class "Default")
      (node (ref "C24") (pin "2") (pinfunction "2_2") (pintype "passive"))
      (node (ref "R8") (pin "1") (pinfunction "1_1") (pintype "passive"))
      (node (ref "S1") (pin "16") (pinfunction "SIM-CLK_16") (pintype "bidirectional"))
    )
    (net (code "52") (name "Net-(S1-SIM-DATA)") (class "Default")
      (node (ref "C26") (pin "2") (pinfunction "2_2") (pintype "passive"))
      (node (ref "R9") (pin "1") (pinfunction "1_1") (pintype "passive"))
      (node (ref "S1") (pin "15") (pinfunction "SIM-DATA_15") (pintype "bidirectional"))
    )
    (net (code "53") (name "Net-(S1-SIM-RST)") (class "Default")
      (node (ref "C25") (pin "2") (pinfunction "2_2") (pintype "passive"))
      (node (ref "R7") (pin "1") (pinfunction "1_1") (pintype "passive"))
      (node (ref "S1") (pin "17") (pinfunction "SIM-RST_17") (pintype "bidirectional"))
    )
    (net (code "54") (name "Net-(S1-VRTC)") (class "Default")
      (node (ref "C22") (pin "+") (pinfunction "+_+") (pintype "passive"))
      (node (ref "S1") (pin "28") (pinfunction "VRTC_28") (pintype "bidirectional"))
    )
    (net (code "55") (name "Net-(U$1-V3)") (class "Default")
      (node (ref "C16") (pin "2") (pinfunction "2_2") (pintype "passive"))
      (node (ref "U$1") (pin "4") (pinfunction "V3_4") (pintype "bidirectional"))
    )
    (net (code "56") (name "Net-(U$1-XI)") (class "Default")
      (node (ref "C14") (pin "2") (pinfunction "2_2") (pintype "passive"))
      (node (ref "Q3") (pin "2") (pinfunction "2_2") (pintype "passive"))
      (node (ref "U$1") (pin "7") (pinfunction "XI_7") (pintype "bidirectional"))
    )
    (net (code "57") (name "Net-(U$1-XO)") (class "Default")
      (node (ref "C15") (pin "2") (pinfunction "2_2") (pintype "passive"))
      (node (ref "Q3") (pin "1") (pinfunction "1_1") (pintype "passive"))
      (node (ref "U$1") (pin "8") (pinfunction "XO_8") (pintype "bidirectional"))
    )
    (net (code "58") (name "PWR4V2_ON") (class "Default")
      (node (ref "IC2") (pin "1") (pinfunction "EN_1") (pintype "bidirectional"))
      (node (ref "IC3") (pin "15") (pinfunction "(OC2B/ICP/PCINT30)PD6_15") (pintype "bidirectional"))
    )
    (net (code "59") (name "RELAY") (class "Default")
      (node (ref "IC3") (pin "42") (pinfunction "(INT2/AIN0/PCINT10)PB2_42") (pintype "bidirectional"))
      (node (ref "R11") (pin "2") (pinfunction "2_2") (pintype "passive"))
    )
    (net (code "60") (name "RESET") (class "Default")
      (node (ref "C12") (pin "1") (pinfunction "1_1") (pintype "passive"))
      (node (ref "U$1") (pin "13") (pinfunction "DTR_13") (pintype "bidirectional"))
    )
    (net (code "61") (name "RX") (class "Default")
      (node (ref "IC3") (pin "9") (pinfunction "(RXD0/PCINT24)PD0_9") (pintype "bidirectional"))
      (node (ref "U$1") (pin "2") (pinfunction "TX_2") (pintype "bidirectional"))
    )
    (net (code "62") (name "SCK") (class "Default")
      (node (ref "IC3") (pin "3") (pinfunction "(SCK/PCINT15)PB7_3") (pintype "bidirectional"))
      (node (ref "U$3") (pin "5") (pinfunction "5.SCK_5") (pintype "bidirectional"))
    )
    (net (code "63") (name "SCL") (class "Default")
      (node (ref "IC3") (pin "19") (pinfunction "(SCL/PCINT16)PC0_19") (pintype "bidirectional"))
      (node (ref "JP2") (pin "2") (pinfunction "2_2") (pintype "passive"))
      (node (ref "R3") (pin "1") (pinfunction "1_1") (pintype "passive"))
    )
    (net (code "64") (name "SDA") (class "Default")
      (node (ref "IC3") (pin "20") (pinfunction "(SDA/PCINT17)PC1_20") (pintype "bidirectional"))
      (node (ref "JP2") (pin "1") (pinfunction "1_1") (pintype "passive"))
      (node (ref "R2") (pin "1") (pinfunction "1_1") (pintype "passive"))
    )
    (net (code "65") (name "TX") (class "Default")
      (node (ref "IC3") (pin "10") (pinfunction "(TXD0/PCINT25)PD1_10") (pintype "bidirectional"))
      (node (ref "U$1") (pin "3") (pinfunction "RX_3") (pintype "bidirectional"))
    )
    (net (code "66") (name "unconnected-(IC1-OUT1-PadTAB)") (class "Default")
      (node (ref "IC1") (pin "TAB") (pinfunction "OUT1_TAB") (pintype "passive"))
    )
    (net (code "67") (name "unconnected-(IC2-TAB-Pad6)") (class "Default")
      (node (ref "IC2") (pin "6") (pinfunction "TAB_6") (pintype "bidirectional"))
    )
    (net (code "68") (name "unconnected-(IC3-(ADC7{slash}PCINT7)PA7-Pad30)") (class "Default")
      (node (ref "IC3") (pin "30") (pinfunction "(ADC7/PCINT7)PA7_30") (pintype "bidirectional"))
    )
    (net (code "69") (name "unconnected-(IC3-(OC2A{slash}PCINT31)PD7-Pad16)") (class "Default")
      (node (ref "IC3") (pin "16") (pinfunction "(OC2A/PCINT31)PD7_16") (pintype "bidirectional"))
    )
    (net (code "70") (name "unconnected-(IC3-(TCK{slash}PCINT18)PC2-Pad21)") (class "Default")
      (node (ref "IC3") (pin "21") (pinfunction "(TCK/PCINT18)PC2_21") (pintype "bidirectional"))
    )
    (net (code "71") (name "unconnected-(IC3-(TDI{slash}PCINT21)PC5-Pad24)") (class "Default")
      (node (ref "IC3") (pin "24") (pinfunction "(TDI/PCINT21)PC5_24") (pintype "bidirectional"))
    )
    (net (code "72") (name "unconnected-(IC3-(TDO{slash}PCINT20)PC4-Pad23)") (class "Default")
      (node (ref "IC3") (pin "23") (pinfunction "(TDO/PCINT20)PC4_23") (pintype "bidirectional"))
    )
    (net (code "73") (name "unconnected-(IC3-(TMS{slash}PCINT19)PC3-Pad22)") (class "Default")
      (node (ref "IC3") (pin "22") (pinfunction "(TMS/PCINT19)PC3_22") (pintype "bidirectional"))
    )
    (net (code "74") (name "unconnected-(IC3-(TOSC1{slash}PCINT22)PC6-Pad25)") (class "Default")
      (node (ref "IC3") (pin "25") (pinfunction "(TOSC1/PCINT22)PC6_25") (pintype "bidirectional"))
    )
    (net (code "75") (name "unconnected-(IC3-(TOSC2{slash}PCINT23)PC7-Pad26)") (class "Default")
      (node (ref "IC3") (pin "26") (pinfunction "(TOSC2/PCINT23)PC7_26") (pintype "bidirectional"))
    )
    (net (code "76") (name "unconnected-(J1-VPP-Pad6)") (class "Default")
      (node (ref "J1") (pin "6") (pinfunction "VPP_6") (pintype "bidirectional"))
    )
    (net (code "77") (name "unconnected-(JP1-ID-Pad4)") (class "Default")
      (node (ref "JP1") (pin "4") (pinfunction "ID_4") (pintype "bidirectional"))
    )
    (net (code "78") (name "unconnected-(S1-ADC-Pad38)") (class "Default")
      (node (ref "S1") (pin "38") (pinfunction "ADC_38") (pintype "bidirectional"))
    )
    (net (code "79") (name "unconnected-(S1-MICN-Pad10)") (class "Default")
      (node (ref "S1") (pin "10") (pinfunction "MICN_10") (pintype "bidirectional"))
    )
    (net (code "80") (name "unconnected-(S1-MICP-Pad9)") (class "Default")
      (node (ref "S1") (pin "9") (pinfunction "MICP_9") (pintype "bidirectional"))
    )
    (net (code "81") (name "unconnected-(S1-RF-SYNC-Pad29)") (class "Default")
      (node (ref "S1") (pin "29") (pinfunction "RF-SYNC_29") (pintype "bidirectional"))
    )
    (net (code "82") (name "unconnected-(S1-SIM-DET-Pad14)") (class "Default")
      (node (ref "S1") (pin "14") (pinfunction "SIM-DET_14") (pintype "bidirectional"))
    )
    (net (code "83") (name "unconnected-(S1-SPKN-Pad12)") (class "Default")
      (node (ref "S1") (pin "12") (pinfunction "SPKN_12") (pintype "bidirectional"))
    )
    (net (code "84") (name "unconnected-(S1-SPKP-Pad11)") (class "Default")
      (node (ref "S1") (pin "11") (pinfunction "SPKP_11") (pintype "bidirectional"))
    )
    (net (code "85") (name "unconnected-(S1-STATUS-Pad42)") (class "Default")
      (node (ref "S1") (pin "42") (pinfunction "STATUS_42") (pintype "bidirectional"))
    )
    (net (code "86") (name "unconnected-(S1-UART1_CTS-Pad4)") (class "Default")
      (node (ref "S1") (pin "4") (pinfunction "UART1_CTS_4") (pintype "bidirectional"))
    )
    (net (code "87") (name "unconnected-(S1-UART1_DCD-Pad5)") (class "Default")
      (node (ref "S1") (pin "5") (pinfunction "UART1_DCD_5") (pintype "bidirectional"))
    )
    (net (code "88") (name "unconnected-(S1-UART1_DTR-Pad6)") (class "Default")
      (node (ref "S1") (pin "6") (pinfunction "UART1_DTR_6") (pintype "bidirectional"))
    )
    (net (code "89") (name "unconnected-(S1-UART1_RTS-Pad3)") (class "Default")
      (node (ref "S1") (pin "3") (pinfunction "UART1_RTS_3") (pintype "bidirectional"))
    )
    (net (code "90") (name "unconnected-(S1-UART2-RXD-Pad23)") (class "Default")
      (node (ref "S1") (pin "23") (pinfunction "UART2-RXD_23") (pintype "bidirectional"))
    )
    (net (code "91") (name "unconnected-(S1-UART2-TXD-Pad22)") (class "Default")
      (node (ref "S1") (pin "22") (pinfunction "UART2-TXD_22") (pintype "bidirectional"))
    )
    (net (code "92") (name "unconnected-(S1-USB-DN-Pad26)") (class "Default")
      (node (ref "S1") (pin "26") (pinfunction "USB-DN_26") (pintype "bidirectional"))
    )
    (net (code "93") (name "unconnected-(S1-USB-DP-Pad25)") (class "Default")
      (node (ref "S1") (pin "25") (pinfunction "USB-DP_25") (pintype "bidirectional"))
    )
    (net (code "94") (name "unconnected-(S1-USB-VBUS-Pad24)") (class "Default")
      (node (ref "S1") (pin "24") (pinfunction "USB-VBUS_24") (pintype "bidirectional"))
    )
    (net (code "95") (name "unconnected-(S1-VD-EXT-Pad40)") (class "Default")
      (node (ref "S1") (pin "40") (pinfunction "VD-EXT_40") (pintype "bidirectional"))
    )
    (net (code "96") (name "unconnected-(U$1-CTS-Pad9)") (class "Default")
      (node (ref "U$1") (pin "9") (pinfunction "CTS_9") (pintype "bidirectional"))
    )
    (net (code "97") (name "unconnected-(U$1-DCD-Pad12)") (class "Default")
      (node (ref "U$1") (pin "12") (pinfunction "DCD_12") (pintype "bidirectional"))
    )
    (net (code "98") (name "unconnected-(U$1-DSR-Pad10)") (class "Default")
      (node (ref "U$1") (pin "10") (pinfunction "DSR_10") (pintype "bidirectional"))
    )
    (net (code "99") (name "unconnected-(U$1-RI-Pad11)") (class "Default")
      (node (ref "U$1") (pin "11") (pinfunction "RI_11") (pintype "bidirectional"))
    )
    (net (code "100") (name "unconnected-(U$1-RS232-Pad15)") (class "Default")
      (node (ref "U$1") (pin "15") (pinfunction "RS232_15") (pintype "bidirectional"))
    )
    (net (code "101") (name "unconnected-(U$1-RTS-Pad14)") (class "Default")
      (node (ref "U$1") (pin "14") (pinfunction "RTS_14") (pintype "bidirectional"))
    )
    (net (code "102") (name "unconnected-(U$3-8.IRQ-Pad8)") (class "Default")
      (node (ref "U$3") (pin "8") (pinfunction "8.IRQ_8") (pintype "bidirectional"))
    )
  )
)
